# bff-v0.net
KiCad netlist of a schematic drawn in EAGLE
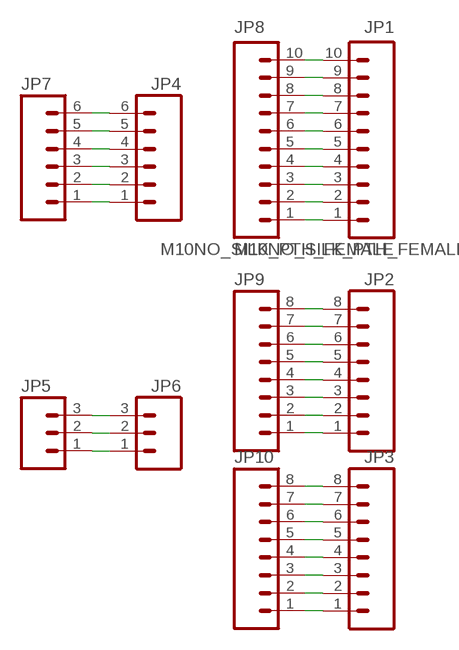
[diagram p0: schematic, sheet 1]

(export (version "E")
  (design (tool "Eeschema 10.0.6"))
  (components
    (comp (ref "JP1")
      (value "M10NO_SILK_PTH_FEMALE")
      (footprint "eagle-import:1X10_NO_SILK")
      (libsource (lib "eagle-import") (part "M10NO_SILK_PTH_FEMALE"))
    )
    (comp (ref "JP2")
      (value "M08NO_SILK_FEMALE_PTH")
      (footprint "eagle-import:1X08_NO_SILK")
      (libsource (lib "eagle-import") (part "M08NO_SILK_FEMALE_PTH"))
    )
    (comp (ref "JP3")
      (value "M08NO_SILK_FEMALE_PTH")
      (footprint "eagle-import:1X08_NO_SILK")
      (libsource (lib "eagle-import") (part "M08NO_SILK_FEMALE_PTH"))
    )
    (comp (ref "JP4")
      (value "M06NO_SILK_FEMALE_PTH")
      (footprint "eagle-import:1X06_NO_SILK")
      (libsource (lib "eagle-import") (part "M06NO_SILK_FEMALE_PTH"))
    )
    (comp (ref "JP5")
      (value "M03LOCK_NO_SILK")
      (footprint "eagle-import:1X03_LOCK_NO_SILK")
      (libsource (lib "eagle-import") (part "M03LOCK_NO_SILK"))
    )
    (comp (ref "JP6")
      (value "M03PTH")
      (footprint "eagle-import:1X03")
      (libsource (lib "eagle-import") (part "M03PTH"))
    )
    (comp (ref "JP7")
      (value "M06NO_SILK_FEMALE_PTH")
      (footprint "eagle-import:1X06_NO_SILK")
      (libsource (lib "eagle-import") (part "M06NO_SILK_FEMALE_PTH"))
    )
    (comp (ref "JP8")
      (value "M10NO_SILK_PTH_FEMALE")
      (footprint "eagle-import:1X10_NO_SILK")
      (libsource (lib "eagle-import") (part "M10NO_SILK_PTH_FEMALE"))
    )
    (comp (ref "JP9")
      (value "M08NO_SILK_FEMALE_PTH")
      (footprint "eagle-import:1X08_NO_SILK")
      (libsource (lib "eagle-import") (part "M08NO_SILK_FEMALE_PTH"))
    )
    (comp (ref "JP10")
      (value "M08NO_SILK_FEMALE_PTH")
      (footprint "eagle-import:1X08_NO_SILK")
      (libsource (lib "eagle-import") (part "M08NO_SILK_FEMALE_PTH"))
    )
  )
  (nets
    (net (code "1") (name "Net-(JP1-Pad1)") (class "Default")
      (node (ref "JP1") (pin "1") (pinfunction "1_1") (pintype "passive"))
      (node (ref "JP8") (pin "1") (pinfunction "1_1") (pintype "passive"))
    )
    (net (code "2") (name "Net-(JP1-Pad2)") (class "Default")
      (node (ref "JP1") (pin "2") (pinfunction "2_2") (pintype "passive"))
      (node (ref "JP8") (pin "2") (pinfunction "2_2") (pintype "passive"))
    )
    (net (code "3") (name "Net-(JP1-Pad3)") (class "Default")
      (node (ref "JP1") (pin "3") (pinfunction "3_3") (pintype "passive"))
      (node (ref "JP8") (pin "3") (pinfunction "3_3") (pintype "passive"))
    )
    (net (code "4") (name "Net-(JP1-Pad4)") (class "Default")
      (node (ref "JP1") (pin "4") (pinfunction "4_4") (pintype "passive"))
      (node (ref "JP8") (pin "4") (pinfunction "4_4") (pintype "passive"))
    )
    (net (code "5") (name "Net-(JP1-Pad5)") (class "Default")
      (node (ref "JP1") (pin "5") (pinfunction "5_5") (pintype "passive"))
      (node (ref "JP8") (pin "5") (pinfunction "5_5") (pintype "passive"))
    )
    (net (code "6") (name "Net-(JP1-Pad6)") (class "Default")
      (node (ref "JP1") (pin "6") (pinfunction "6_6") (pintype "passive"))
      (node (ref "JP8") (pin "6") (pinfunction "6_6") (pintype "passive"))
    )
    (net (code "7") (name "Net-(JP1-Pad7)") (class "Default")
      (node (ref "JP1") (pin "7") (pinfunction "7_7") (pintype "passive"))
      (node (ref "JP8") (pin "7") (pinfunction "7_7") (pintype "passive"))
    )
    (net (code "8") (name "Net-(JP1-Pad8)") (class "Default")
      (node (ref "JP1") (pin "8") (pinfunction "8_8") (pintype "passive"))
      (node (ref "JP8") (pin "8") (pinfunction "8_8") (pintype "passive"))
    )
    (net (code "9") (name "Net-(JP1-Pad9)") (class "Default")
      (node (ref "JP1") (pin "9") (pinfunction "9_9") (pintype "passive"))
      (node (ref "JP8") (pin "9") (pinfunction "9_9") (pintype "passive"))
    )
    (net (code "10") (name "Net-(JP1-Pad10)") (class "Default")
      (node (ref "JP1") (pin "10") (pinfunction "10_10") (pintype "passive"))
      (node (ref "JP8") (pin "10") (pinfunction "10_10") (pintype "passive"))
    )
    (net (code "11") (name "Net-(JP2-Pad1)") (class "Default")
      (node (ref "JP2") (pin "1") (pinfunction "1_1") (pintype "passive"))
      (node (ref "JP9") (pin "1") (pinfunction "1_1") (pintype "passive"))
    )
    (net (code "12") (name "Net-(JP2-Pad2)") (class "Default")
      (node (ref "JP2") (pin "2") (pinfunction "2_2") (pintype "passive"))
      (node (ref "JP9") (pin "2") (pinfunction "2_2") (pintype "passive"))
    )
    (net (code "13") (name "Net-(JP2-Pad3)") (class "Default")
      (node (ref "JP2") (pin "3") (pinfunction "3_3") (pintype "passive"))
      (node (ref "JP9") (pin "3") (pinfunction "3_3") (pintype "passive"))
    )
    (net (code "14") (name "Net-(JP2-Pad4)") (class "Default")
      (node (ref "JP2") (pin "4") (pinfunction "4_4") (pintype "passive"))
      (node (ref "JP9") (pin "4") (pinfunction "4_4") (pintype "passive"))
    )
    (net (code "15") (name "Net-(JP2-Pad5)") (class "Default")
      (node (ref "JP2") (pin "5") (pinfunction "5_5") (pintype "passive"))
      (node (ref "JP9") (pin "5") (pinfunction "5_5") (pintype "passive"))
    )
    (net (code "16") (name "Net-(JP2-Pad6)") (class "Default")
      (node (ref "JP2") (pin "6") (pinfunction "6_6") (pintype "passive"))
      (node (ref "JP9") (pin "6") (pinfunction "6_6") (pintype "passive"))
    )
    (net (code "17") (name "Net-(JP2-Pad7)") (class "Default")
      (node (ref "JP2") (pin "7") (pinfunction "7_7") (pintype "passive"))
      (node (ref "JP9") (pin "7") (pinfunction "7_7") (pintype "passive"))
    )
    (net (code "18") (name "Net-(JP2-Pad8)") (class "Default")
      (node (ref "JP2") (pin "8") (pinfunction "8_8") (pintype "passive"))
      (node (ref "JP9") (pin "8") (pinfunction "8_8") (pintype "passive"))
    )
    (net (code "19") (name "Net-(JP4-Pad1)") (class "Default")
      (node (ref "JP4") (pin "1") (pinfunction "1_1") (pintype "passive"))
      (node (ref "JP7") (pin "1") (pinfunction "1_1") (pintype "passive"))
    )
    (net (code "20") (name "Net-(JP4-Pad2)") (class "Default")
      (node (ref "JP4") (pin "2") (pinfunction "2_2") (pintype "passive"))
      (node (ref "JP7") (pin "2") (pinfunction "2_2") (pintype "passive"))
    )
    (net (code "21") (name "Net-(JP4-Pad3)") (class "Default")
      (node (ref "JP4") (pin "3") (pinfunction "3_3") (pintype "passive"))
      (node (ref "JP7") (pin "3") (pinfunction "3_3") (pintype "passive"))
    )
    (net (code "22") (name "Net-(JP4-Pad4)") (class "Default")
      (node (ref "JP4") (pin "4") (pinfunction "4_4") (pintype "passive"))
      (node (ref "JP7") (pin "4") (pinfunction "4_4") (pintype "passive"))
    )
    (net (code "23") (name "Net-(JP4-Pad5)") (class "Default")
      (node (ref "JP4") (pin "5") (pinfunction "5_5") (pintype "passive"))
      (node (ref "JP7") (pin "5") (pinfunction "5_5") (pintype "passive"))
    )
    (net (code "24") (name "Net-(JP4-Pad6)") (class "Default")
      (node (ref "JP4") (pin "6") (pinfunction "6_6") (pintype "passive"))
      (node (ref "JP7") (pin "6") (pinfunction "6_6") (pintype "passive"))
    )
    (net (code "25") (name "Net-(JP5-Pad1)") (class "Default")
      (node (ref "JP5") (pin "1") (pinfunction "1_1") (pintype "passive"))
      (node (ref "JP6") (pin "1") (pinfunction "1_1") (pintype "passive"))
    )
    (net (code "26") (name "Net-(JP5-Pad2)") (class "Default")
      (node (ref "JP5") (pin "2") (pinfunction "2_2") (pintype "passive"))
      (node (ref "JP6") (pin "2") (pinfunction "2_2") (pintype "passive"))
    )
    (net (code "27") (name "Net-(JP5-Pad3)") (class "Default")
      (node (ref "JP5") (pin "3") (pinfunction "3_3") (pintype "passive"))
      (node (ref "JP6") (pin "3") (pinfunction "3_3") (pintype "passive"))
    )
    (net (code "28") (name "Net-(JP10-Pad1)") (class "Default")
      (node (ref "JP10") (pin "1") (pinfunction "1_1") (pintype "passive"))
      (node (ref "JP3") (pin "1") (pinfunction "1_1") (pintype "passive"))
    )
    (net (code "29") (name "Net-(JP10-Pad2)") (class "Default")
      (node (ref "JP10") (pin "2") (pinfunction "2_2") (pintype "passive"))
      (node (ref "JP3") (pin "2") (pinfunction "2_2") (pintype "passive"))
    )
    (net (code "30") (name "Net-(JP10-Pad3)") (class "Default")
      (node (ref "JP10") (pin "3") (pinfunction "3_3") (pintype "passive"))
      (node (ref "JP3") (pin "3") (pinfunction "3_3") (pintype "passive"))
    )
    (net (code "31") (name "Net-(JP10-Pad4)") (class "Default")
      (node (ref "JP10") (pin "4") (pinfunction "4_4") (pintype "passive"))
      (node (ref "JP3") (pin "4") (pinfunction "4_4") (pintype "passive"))
    )
    (net (code "32") (name "Net-(JP10-Pad5)") (class "Default")
      (node (ref "JP10") (pin "5") (pinfunction "5_5") (pintype "passive"))
      (node (ref "JP3") (pin "5") (pinfunction "5_5") (pintype "passive"))
    )
    (net (code "33") (name "Net-(JP10-Pad6)") (class "Default")
      (node (ref "JP10") (pin "6") (pinfunction "6_6") (pintype "passive"))
      (node (ref "JP3") (pin "6") (pinfunction "6_6") (pintype "passive"))
    )
    (net (code "34") (name "Net-(JP10-Pad7)") (class "Default")
      (node (ref "JP10") (pin "7") (pinfunction "7_7") (pintype "passive"))
      (node (ref "JP3") (pin "7") (pinfunction "7_7") (pintype "passive"))
    )
    (net (code "35") (name "Net-(JP10-Pad8)") (class "Default")
      (node (ref "JP10") (pin "8") (pinfunction "8_8") (pintype "passive"))
      (node (ref "JP3") (pin "8") (pinfunction "8_8") (pintype "passive"))
    )
  )
)
